# Driver.net
KiCad netlist of a schematic drawn in EasyEDA Pro
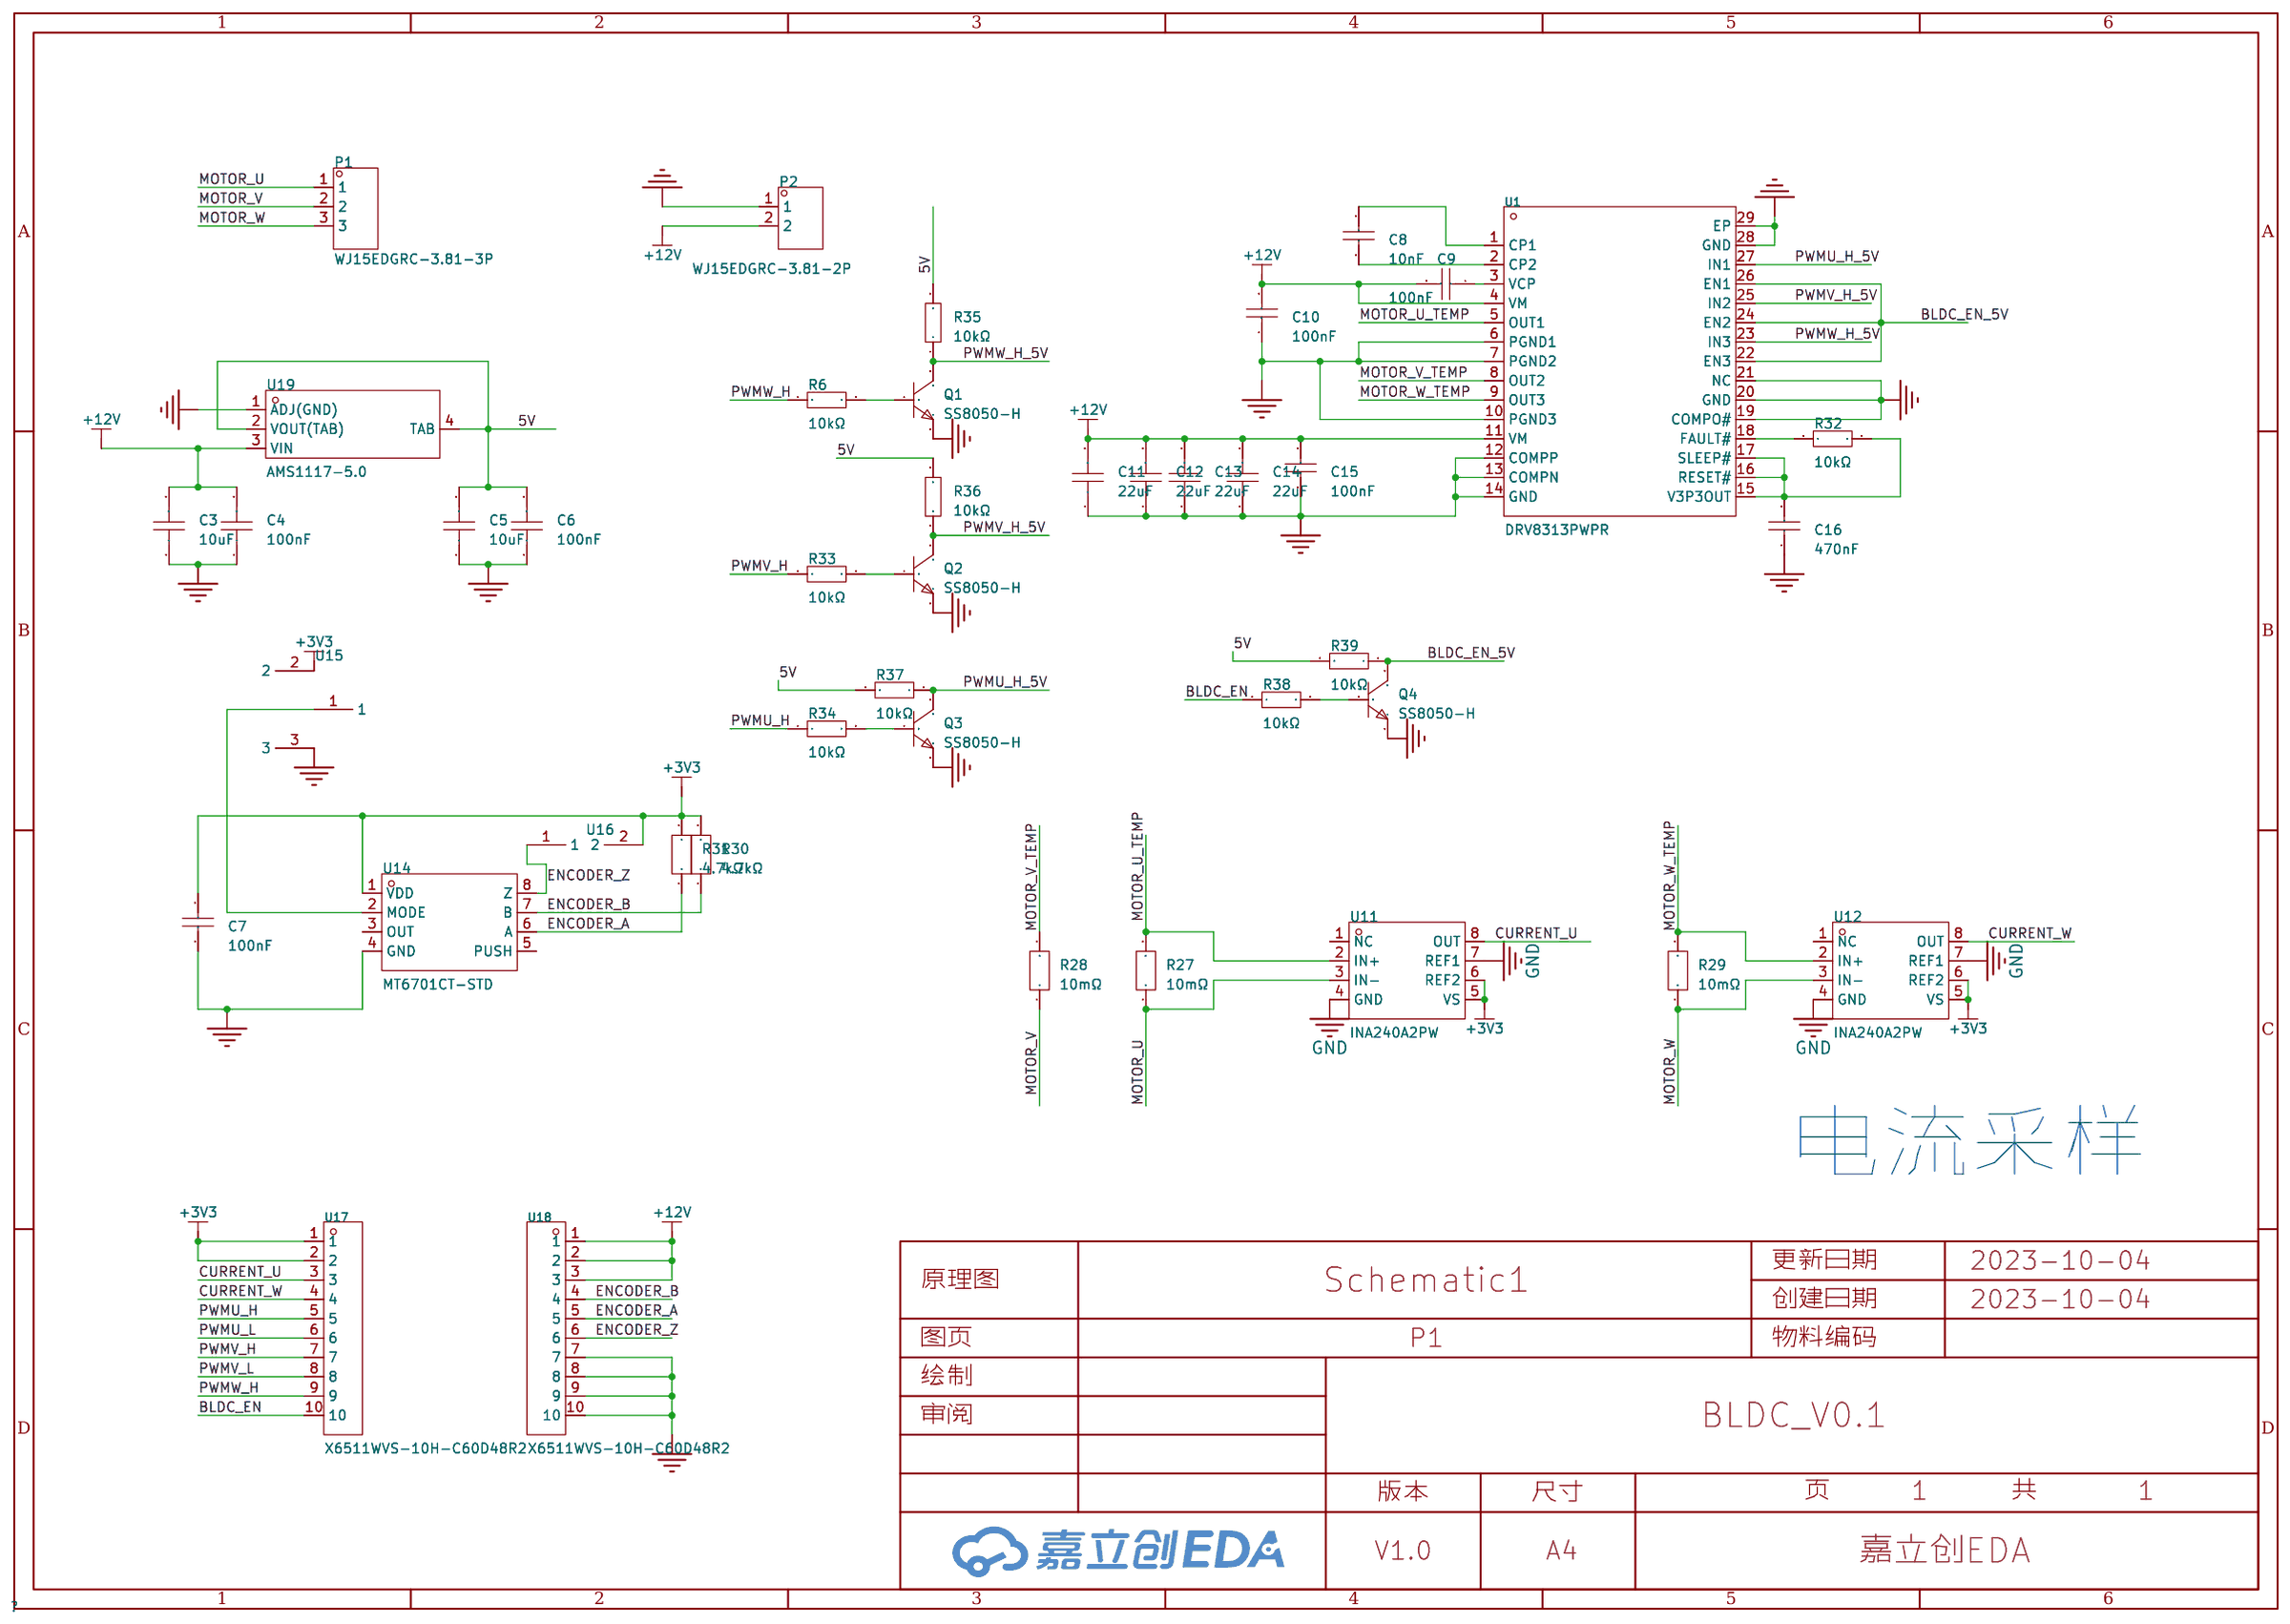
[diagram p0: schematic sheet]

(export (version "E")
  (design (tool "Eeschema 10.0.6"))
  (components
    (comp (ref "C3")
      (value "10uF")
      (footprint "easyedapro:C0603")
      (description "容值:10uF;精度:±20%;额定电压:25V;材质(温度系数):X5R;")
      (fields
        (field (name "Manufacturer Part") "CL10A106MA8NRNC")
        (field (name "Manufacturer") "SAMSUNG(三星)")
      )
      (libsource (lib "easyedapro") (part "CL10A106MA8NRNC"))
    )
    (comp (ref "C4")
      (value "100nF")
      (footprint "easyedapro:C0603")
      (description "容值:100nF;精度:±10%;额定电压:50V;材质(温度系数):X7R;")
      (fields
        (field (name "Manufacturer Part") "CC0603KRX7R9BB104")
        (field (name "Manufacturer") "YAGEO(国巨)")
      )
      (libsource (lib "easyedapro") (part "CC0603KRX7R9BB104"))
    )
    (comp (ref "C5")
      (value "10uF")
      (footprint "easyedapro:C0603")
      (description "容值:10uF;精度:±20%;额定电压:25V;材质(温度系数):X5R;")
      (fields
        (field (name "Manufacturer Part") "CL10A106MA8NRNC")
        (field (name "Manufacturer") "SAMSUNG(三星)")
      )
      (libsource (lib "easyedapro") (part "CL10A106MA8NRNC"))
    )
    (comp (ref "C6")
      (value "100nF")
      (footprint "easyedapro:C0603")
      (description "容值:100nF;精度:±10%;额定电压:50V;材质(温度系数):X7R;")
      (fields
        (field (name "Manufacturer Part") "CC0603KRX7R9BB104")
        (field (name "Manufacturer") "YAGEO(国巨)")
      )
      (libsource (lib "easyedapro") (part "CC0603KRX7R9BB104"))
    )
    (comp (ref "C7")
      (value "100nF")
      (footprint "easyedapro:C0603")
      (description "容值:100nF;精度:±10%;额定电压:50V;材质(温度系数):X7R;")
      (fields (field (name "Manufacturer Part") "0603B104K500NT") (field (name "Manufacturer") "FH(风华)"))
      (libsource (lib "easyedapro") (part "0603B104K500NT"))
    )
    (comp (ref "C8")
      (value "10nF")
      (footprint "easyedapro:C0603")
      (description "容值:10nF;精度:±10%;额定电压:50V;材质(温度系数):X7R;")
      (fields
        (field (name "Manufacturer Part") "CC0603KRX7R9BB103")
        (field (name "Manufacturer") "YAGEO(国巨)")
      )
      (libsource (lib "easyedapro") (part "CC0603KRX7R9BB103"))
    )
    (comp (ref "C9")
      (value "100nF")
      (footprint "easyedapro:C0603")
      (description "容值:100nF;精度:±10%;额定电压:50V;材质(温度系数):X7R;")
      (fields (field (name "Manufacturer Part") "0603B104K500NT") (field (name "Manufacturer") "FH(风华)"))
      (libsource (lib "easyedapro") (part "0603B104K500NT"))
    )
    (comp (ref "C10")
      (value "100nF")
      (footprint "easyedapro:C0603")
      (description "容值:100nF;精度:±10%;额定电压:50V;材质(温度系数):X7R;")
      (fields (field (name "Manufacturer Part") "0603B104K500NT") (field (name "Manufacturer") "FH(风华)"))
      (libsource (lib "easyedapro") (part "0603B104K500NT"))
    )
    (comp (ref "C11")
      (value "22uF")
      (footprint "easyedapro:C0805")
      (description "容值:22uF;精度:±20%;额定电压:25V;材质(温度系数):X5R;")
      (fields
        (field (name "Manufacturer Part") "CL21A226MAQNNNE")
        (field (name "Manufacturer") "SAMSUNG(三星)")
      )
      (libsource (lib "easyedapro") (part "CL21A226MAQNNNE"))
    )
    (comp (ref "C12")
      (value "22uF")
      (footprint "easyedapro:C0805")
      (description "容值:22uF;精度:±20%;额定电压:25V;材质(温度系数):X5R;")
      (fields
        (field (name "Manufacturer Part") "CL21A226MAQNNNE")
        (field (name "Manufacturer") "SAMSUNG(三星)")
      )
      (libsource (lib "easyedapro") (part "CL21A226MAQNNNE"))
    )
    (comp (ref "C13")
      (value "22uF")
      (footprint "easyedapro:C0805")
      (description "容值:22uF;精度:±20%;额定电压:25V;材质(温度系数):X5R;")
      (fields
        (field (name "Manufacturer Part") "CL21A226MAQNNNE")
        (field (name "Manufacturer") "SAMSUNG(三星)")
      )
      (libsource (lib "easyedapro") (part "CL21A226MAQNNNE"))
    )
    (comp (ref "C14")
      (value "22uF")
      (footprint "easyedapro:C0805")
      (description "容值:22uF;精度:±20%;额定电压:25V;材质(温度系数):X5R;")
      (fields
        (field (name "Manufacturer Part") "CL21A226MAQNNNE")
        (field (name "Manufacturer") "SAMSUNG(三星)")
      )
      (libsource (lib "easyedapro") (part "CL21A226MAQNNNE"))
    )
    (comp (ref "C15")
      (value "100nF")
      (footprint "easyedapro:C0603")
      (description "容值:100nF;精度:±10%;额定电压:50V;材质(温度系数):X7R;")
      (fields (field (name "Manufacturer Part") "0603B104K500NT") (field (name "Manufacturer") "FH(风华)"))
      (libsource (lib "easyedapro") (part "0603B104K500NT"))
    )
    (comp (ref "C16")
      (value "470nF")
      (footprint "easyedapro:C0603")
      (description "容值:470nF;精度:±10%;额定电压:25V;材质(温度系数):X7R;")
      (fields
        (field (name "Manufacturer Part") "CL10B474KA8NNNC")
        (field (name "Manufacturer") "SAMSUNG(三星)")
      )
      (libsource (lib "easyedapro") (part "CL10B474KA8NNNC"))
    )
    (comp (ref "P1")
      (value "WJ15EDGRC-3.81-3P")
      (footprint "easyedapro:CONN-TH_3P-P3.81_WJ15EDGRC-3.81-3P")
      (description "连接器类型:板端/插座-闭口;结构:1x3P;间距:3.81mm;排数:1;每排PIN数:3;安装方式:弯针;颜色:绿色;")
      (fields (field (name "Manufacturer") "KANGNEX(康奈克斯电气)"))
      (libsource (lib "easyedapro") (part "WJ15EDGRC-3.81-3P"))
    )
    (comp (ref "P2")
      (value "WJ15EDGRC-3.81-2P")
      (footprint "easyedapro:CONN-TH_2P-P3.81_WJ15EDGRC-3.81-2P")
      (description "连接器类型:板端/插座-闭口;间距:3.81mm;排数:1;每排PIN数:2;安装方式:弯针;颜色:绿色;")
      (fields (field (name "Manufacturer") "KANGNEX(康奈克斯电气)"))
      (libsource (lib "easyedapro") (part "WJ15EDGRC-3.81-2P"))
    )
    (comp (ref "Q1")
      (value "SS8050-H")
      (footprint "easyedapro:SOT-23-3_L2.9-W1.3-P1.90-LS2.4-BR")
      (description "晶体管类型:NPN;集射极击穿电压(Vceo):25V;集电极电流(Ic):1.5A;功率(Pd):300mW;直流电流增益(hFE@Ic,Vce):200@100mA,1V;")
      (fields (field (name "Manufacturer") "YANGJIE(扬杰)"))
      (libsource (lib "easyedapro") (part "SS8050-H"))
    )
    (comp (ref "Q2")
      (value "SS8050-H")
      (footprint "easyedapro:SOT-23-3_L2.9-W1.3-P1.90-LS2.4-BR")
      (description "晶体管类型:NPN;集射极击穿电压(Vceo):25V;集电极电流(Ic):1.5A;功率(Pd):300mW;直流电流增益(hFE@Ic,Vce):200@100mA,1V;")
      (fields (field (name "Manufacturer") "YANGJIE(扬杰)"))
      (libsource (lib "easyedapro") (part "SS8050-H"))
    )
    (comp (ref "Q3")
      (value "SS8050-H")
      (footprint "easyedapro:SOT-23-3_L2.9-W1.3-P1.90-LS2.4-BR")
      (description "晶体管类型:NPN;集射极击穿电压(Vceo):25V;集电极电流(Ic):1.5A;功率(Pd):300mW;直流电流增益(hFE@Ic,Vce):200@100mA,1V;")
      (fields (field (name "Manufacturer") "YANGJIE(扬杰)"))
      (libsource (lib "easyedapro") (part "SS8050-H"))
    )
    (comp (ref "Q4")
      (value "SS8050-H")
      (footprint "easyedapro:SOT-23-3_L2.9-W1.3-P1.90-LS2.4-BR")
      (description "晶体管类型:NPN;集射极击穿电压(Vceo):25V;集电极电流(Ic):1.5A;功率(Pd):300mW;直流电流增益(hFE@Ic,Vce):200@100mA,1V;")
      (fields (field (name "Manufacturer") "YANGJIE(扬杰)"))
      (libsource (lib "easyedapro") (part "SS8050-H"))
    )
    (comp (ref "R6")
      (value "10kΩ")
      (footprint "easyedapro:R0603")
      (description "电阻类型:厚膜电阻;阻值:10kΩ;精度:±1%;功率:100mW;")
      (fields (field (name "Manufacturer Part") "ERJ3EKF1002V") (field (name "Manufacturer") "PANASONIC(松下)"))
      (libsource (lib "easyedapro") (part "ERJ-3EKF1002V"))
    )
    (comp (ref "R27")
      (value "10mΩ")
      (footprint "easyedapro:RES-SMD_L6.4-W3.2-R2512")
      (description "阻值:10mΩ;功率:3W;")
      (fields
        (field (name "Manufacturer Part") "HoJLR2512-3W-10mR-1%")
        (field (name "Manufacturer") "Milliohm(毫欧)")
      )
      (libsource (lib "easyedapro") (part "HOJLR2512-3W-10MR-1%"))
    )
    (comp (ref "R28")
      (value "10mΩ")
      (footprint "easyedapro:RES-SMD_L6.4-W3.2-R2512")
      (description "阻值:10mΩ;功率:3W;")
      (fields
        (field (name "Manufacturer Part") "HoJLR2512-3W-10mR-1%")
        (field (name "Manufacturer") "Milliohm(毫欧)")
      )
      (libsource (lib "easyedapro") (part "HOJLR2512-3W-10MR-1%"))
    )
    (comp (ref "R29")
      (value "10mΩ")
      (footprint "easyedapro:RES-SMD_L6.4-W3.2-R2512")
      (description "阻值:10mΩ;功率:3W;")
      (fields
        (field (name "Manufacturer Part") "HoJLR2512-3W-10mR-1%")
        (field (name "Manufacturer") "Milliohm(毫欧)")
      )
      (libsource (lib "easyedapro") (part "HOJLR2512-3W-10MR-1%"))
    )
    (comp (ref "R30")
      (value "4.7kΩ")
      (footprint "easyedapro:R0603")
      (description "阻值:4.7kΩ;功率:100mW;")
      (fields
        (field (name "Manufacturer Part") "HoLTT0603-1/10W-4.7K-1%")
        (field (name "Manufacturer") "Milliohm(毫欧)")
      )
      (libsource (lib "easyedapro") (part "HOLTT0603-1/10W-4.7K-1%"))
    )
    (comp (ref "R31")
      (value "4.7kΩ")
      (footprint "easyedapro:R0603")
      (description "阻值:4.7kΩ;功率:100mW;")
      (fields
        (field (name "Manufacturer Part") "HoLTT0603-1/10W-4.7K-1%")
        (field (name "Manufacturer") "Milliohm(毫欧)")
      )
      (libsource (lib "easyedapro") (part "HOLTT0603-1/10W-4.7K-1%"))
    )
    (comp (ref "R32")
      (value "10kΩ")
      (footprint "easyedapro:R0603")
      (description "电阻类型:厚膜电阻;阻值:10kΩ;精度:±1%;功率:100mW;")
      (fields
        (field (name "Manufacturer Part") "0603WAF1002T5E")
        (field (name "Manufacturer") "UNI-ROYAL(厚声)")
      )
      (libsource (lib "easyedapro") (part "0603WAF1002T5E"))
    )
    (comp (ref "R33")
      (value "10kΩ")
      (footprint "easyedapro:R0603")
      (description "电阻类型:厚膜电阻;阻值:10kΩ;精度:±1%;功率:100mW;")
      (fields (field (name "Manufacturer Part") "ERJ3EKF1002V") (field (name "Manufacturer") "PANASONIC(松下)"))
      (libsource (lib "easyedapro") (part "ERJ-3EKF1002V"))
    )
    (comp (ref "R34")
      (value "10kΩ")
      (footprint "easyedapro:R0603")
      (description "电阻类型:厚膜电阻;阻值:10kΩ;精度:±1%;功率:100mW;")
      (fields (field (name "Manufacturer Part") "ERJ3EKF1002V") (field (name "Manufacturer") "PANASONIC(松下)"))
      (libsource (lib "easyedapro") (part "ERJ-3EKF1002V"))
    )
    (comp (ref "R35")
      (value "10kΩ")
      (footprint "easyedapro:R0603")
      (description "电阻类型:厚膜电阻;阻值:10kΩ;精度:±1%;功率:100mW;")
      (fields (field (name "Manufacturer Part") "ERJ3EKF1002V") (field (name "Manufacturer") "PANASONIC(松下)"))
      (libsource (lib "easyedapro") (part "ERJ-3EKF1002V"))
    )
    (comp (ref "R36")
      (value "10kΩ")
      (footprint "easyedapro:R0603")
      (description "电阻类型:厚膜电阻;阻值:10kΩ;精度:±1%;功率:100mW;")
      (fields (field (name "Manufacturer Part") "ERJ3EKF1002V") (field (name "Manufacturer") "PANASONIC(松下)"))
      (libsource (lib "easyedapro") (part "ERJ-3EKF1002V"))
    )
    (comp (ref "R37")
      (value "10kΩ")
      (footprint "easyedapro:R0603")
      (description "电阻类型:厚膜电阻;阻值:10kΩ;精度:±1%;功率:100mW;")
      (fields (field (name "Manufacturer Part") "ERJ3EKF1002V") (field (name "Manufacturer") "PANASONIC(松下)"))
      (libsource (lib "easyedapro") (part "ERJ-3EKF1002V"))
    )
    (comp (ref "R38")
      (value "10kΩ")
      (footprint "easyedapro:R0603")
      (description "电阻类型:厚膜电阻;阻值:10kΩ;精度:±1%;功率:100mW;")
      (fields (field (name "Manufacturer Part") "ERJ3EKF1002V") (field (name "Manufacturer") "PANASONIC(松下)"))
      (libsource (lib "easyedapro") (part "ERJ-3EKF1002V"))
    )
    (comp (ref "R39")
      (value "10kΩ")
      (footprint "easyedapro:R0603")
      (description "电阻类型:厚膜电阻;阻值:10kΩ;精度:±1%;功率:100mW;")
      (fields (field (name "Manufacturer Part") "ERJ3EKF1002V") (field (name "Manufacturer") "PANASONIC(松下)"))
      (libsource (lib "easyedapro") (part "ERJ-3EKF1002V"))
    )
    (comp (ref "U1")
      (value "DRV8313PWPR")
      (footprint "easyedapro:HTSSOP-28_L9.8-W4.5-P0.65-LS6.6-BL-EP")
      (description "类型:无刷直流BLDC;电源电压:8V~60V;输出电流:-;接口:并行;")
      (fields (field (name "Manufacturer") "TI(德州仪器)"))
      (libsource (lib "easyedapro") (part "DRV8313PWPR"))
    )
    (comp (ref "U11")
      (value "INA240A2PW")
      (footprint "easyedapro:TSSOP-8_L4.4-W3.0-P0.65-LS6.4-BR")
      (description "具有增强的 PWM 抑制能力的 -4V 至 80V、双向、超精密电流感应放大器 8-TSSOP -40 to 125")
      (fields (field (name "Manufacturer") "TI(德州仪器)"))
      (libsource (lib "easyedapro") (part "INA240A2PW"))
    )
    (comp (ref "U12")
      (value "INA240A2PW")
      (footprint "easyedapro:TSSOP-8_L4.4-W3.0-P0.65-LS6.4-BR")
      (description "具有增强的 PWM 抑制能力的 -4V 至 80V、双向、超精密电流感应放大器 8-TSSOP -40 to 125")
      (fields (field (name "Manufacturer") "TI(德州仪器)"))
      (libsource (lib "easyedapro") (part "INA240A2PW"))
    )
    (comp (ref "U14")
      (value "MT6701CT-STD")
      (footprint "easyedapro:SOP-8_L4.9-W3.9-P1.27-LS6.0-BL")
      (description "磁性编码器 磁性编码开关 磁性角度检测IC 可编程磁性角度位置芯片")
      (fields (field (name "Manufacturer") "MagnTek(麦歌恩)"))
      (libsource (lib "easyedapro") (part "MT6701CT-STD"))
    )
    (comp (ref "U15")
      (value "~")
      (footprint "easyedapro:三端短接调试")
      (libsource (lib "easyedapro") (part "三段短接调试"))
    )
    (comp (ref "U16")
      (value "~")
      (footprint "easyedapro:两端短接调试位")
      (libsource (lib "easyedapro") (part "两端短接调试位"))
    )
    (comp (ref "U17")
      (value "X6511WVS-10H-C60D48R2")
      (footprint "easyedapro:HDR-SMD_10P-P2.54-V-M-LS4.8_R2")
      (fields (field (name "Manufacturer") "XKB Connectivity(中国星坤)"))
      (libsource (lib "easyedapro") (part "X6511WVS-10H-C60D48R2"))
    )
    (comp (ref "U18")
      (value "X6511WVS-10H-C60D48R2")
      (footprint "easyedapro:HDR-SMD_10P-P2.54-V-M-LS4.8_R2")
      (fields (field (name "Manufacturer") "XKB Connectivity(中国星坤)"))
      (libsource (lib "easyedapro") (part "X6511WVS-10H-C60D48R2"))
    )
    (comp (ref "U19")
      (value "AMS1117-5.0")
      (footprint "easyedapro:SOT-223_L6.7-W3.5-P2.30-BR")
      (description "输出类型:固定;输出极性:正;最大输入电压:18V;输出电压:5V;输出电流:1A;电源纹波抑制比(PSRR):60dB@(120Hz);")
      (fields (field (name "Manufacturer") "UMW(广东友台半导体)"))
      (libsource (lib "easyedapro") (part "AMS1117-5.0_C347223"))
    )
  )
  (nets
    (net (code "1") (name "+3V3") (class "Default")
      (node (ref "C7") (pin "2") (pinfunction "2_2") (pintype "input"))
      (node (ref "R30") (pin "2") (pinfunction "2_2") (pintype "input"))
      (node (ref "R31") (pin "2") (pinfunction "2_2") (pintype "input"))
      (node (ref "U11") (pin "5") (pinfunction "VS_5") (pintype "input"))
      (node (ref "U11") (pin "6") (pinfunction "REF2_6") (pintype "input"))
      (node (ref "U12") (pin "5") (pinfunction "VS_5") (pintype "input"))
      (node (ref "U12") (pin "6") (pinfunction "REF2_6") (pintype "input"))
      (node (ref "U14") (pin "1") (pinfunction "VDD_1") (pintype "input"))
      (node (ref "U15") (pin "2") (pinfunction "2_2") (pintype "input"))
      (node (ref "U16") (pin "2") (pinfunction "2_2") (pintype "input"))
      (node (ref "U17") (pin "1") (pinfunction "1_1") (pintype "input"))
      (node (ref "U17") (pin "2") (pinfunction "2_2") (pintype "input"))
    )
    (net (code "2") (name "+12V") (class "Default")
      (node (ref "C10") (pin "2") (pinfunction "2_2") (pintype "input"))
      (node (ref "C11") (pin "2") (pinfunction "2_2") (pintype "input"))
      (node (ref "C12") (pin "2") (pinfunction "2_2") (pintype "input"))
      (node (ref "C13") (pin "2") (pinfunction "2_2") (pintype "input"))
      (node (ref "C14") (pin "2") (pinfunction "2_2") (pintype "input"))
      (node (ref "C15") (pin "1") (pinfunction "1_1") (pintype "input"))
      (node (ref "C3") (pin "2") (pinfunction "2_2") (pintype "input"))
      (node (ref "C4") (pin "2") (pinfunction "2_2") (pintype "input"))
      (node (ref "C9") (pin "2") (pinfunction "2_2") (pintype "input"))
      (node (ref "P2") (pin "2") (pinfunction "2_2") (pintype "input"))
      (node (ref "U1") (pin "11") (pinfunction "VM_11") (pintype "input"))
      (node (ref "U1") (pin "4") (pinfunction "VM_4") (pintype "input"))
      (node (ref "U18") (pin "1") (pinfunction "1_1") (pintype "input"))
      (node (ref "U18") (pin "2") (pinfunction "2_2") (pintype "input"))
      (node (ref "U18") (pin "3") (pinfunction "3_3") (pintype "input"))
      (node (ref "U19") (pin "3") (pinfunction "VIN_3") (pintype "input"))
    )
    (net (code "3") (name "/5V") (class "Default")
      (node (ref "C5") (pin "2") (pinfunction "2_2") (pintype "input"))
      (node (ref "C6") (pin "2") (pinfunction "2_2") (pintype "input"))
      (node (ref "R35") (pin "2") (pinfunction "2_2") (pintype "input"))
      (node (ref "R36") (pin "2") (pinfunction "2_2") (pintype "input"))
      (node (ref "R37") (pin "2") (pinfunction "2_2") (pintype "input"))
      (node (ref "R39") (pin "2") (pinfunction "2_2") (pintype "input"))
      (node (ref "U19") (pin "2") (pinfunction "VOUT(TAB)_2") (pintype "input"))
      (node (ref "U19") (pin "4") (pinfunction "TAB_4") (pintype "input"))
    )
    (net (code "4") (name "/BLDC_EN") (class "Default")
      (node (ref "R38") (pin "1") (pinfunction "1_1") (pintype "input"))
      (node (ref "U17") (pin "10") (pinfunction "10_10") (pintype "input"))
    )
    (net (code "5") (name "/BLDC_EN_5V") (class "Default")
      (node (ref "Q4") (pin "3") (pinfunction "C_3") (pintype "input"))
      (node (ref "R39") (pin "1") (pinfunction "1_1") (pintype "input"))
      (node (ref "U1") (pin "22") (pinfunction "EN3_22") (pintype "input"))
      (node (ref "U1") (pin "24") (pinfunction "EN2_24") (pintype "input"))
      (node (ref "U1") (pin "26") (pinfunction "EN1_26") (pintype "input"))
    )
    (net (code "6") (name "/CURRENT_U") (class "Default")
      (node (ref "U11") (pin "8") (pinfunction "OUT_8") (pintype "input"))
      (node (ref "U17") (pin "3") (pinfunction "3_3") (pintype "input"))
    )
    (net (code "7") (name "/CURRENT_W") (class "Default")
      (node (ref "U12") (pin "8") (pinfunction "OUT_8") (pintype "input"))
      (node (ref "U17") (pin "4") (pinfunction "4_4") (pintype "input"))
    )
    (net (code "8") (name "/ENCODER_A") (class "Default")
      (node (ref "R31") (pin "1") (pinfunction "1_1") (pintype "input"))
      (node (ref "U14") (pin "6") (pinfunction "A_6") (pintype "input"))
      (node (ref "U18") (pin "5") (pinfunction "5_5") (pintype "input"))
    )
    (net (code "9") (name "/ENCODER_B") (class "Default")
      (node (ref "R30") (pin "1") (pinfunction "1_1") (pintype "input"))
      (node (ref "U14") (pin "7") (pinfunction "B_7") (pintype "input"))
      (node (ref "U18") (pin "4") (pinfunction "4_4") (pintype "input"))
    )
    (net (code "10") (name "/ENCODER_Z") (class "Default")
      (node (ref "U14") (pin "8") (pinfunction "Z_8") (pintype "input"))
      (node (ref "U16") (pin "1") (pinfunction "1_1") (pintype "input"))
      (node (ref "U18") (pin "6") (pinfunction "6_6") (pintype "input"))
    )
    (net (code "11") (name "/MOTOR_U") (class "Default")
      (node (ref "P1") (pin "1") (pinfunction "1_1") (pintype "input"))
      (node (ref "R27") (pin "1") (pinfunction "1_1") (pintype "input"))
      (node (ref "U11") (pin "3") (pinfunction "IN-_3") (pintype "input"))
    )
    (net (code "12") (name "/MOTOR_U_TEMP") (class "Default")
      (node (ref "R27") (pin "2") (pinfunction "2_2") (pintype "input"))
      (node (ref "U1") (pin "5") (pinfunction "OUT1_5") (pintype "input"))
      (node (ref "U11") (pin "2") (pinfunction "IN+_2") (pintype "input"))
    )
    (net (code "13") (name "/MOTOR_V") (class "Default")
      (node (ref "P1") (pin "2") (pinfunction "2_2") (pintype "input"))
      (node (ref "R28") (pin "1") (pinfunction "1_1") (pintype "input"))
    )
    (net (code "14") (name "/MOTOR_V_TEMP") (class "Default")
      (node (ref "R28") (pin "2") (pinfunction "2_2") (pintype "input"))
      (node (ref "U1") (pin "8") (pinfunction "OUT2_8") (pintype "input"))
    )
    (net (code "15") (name "/MOTOR_W") (class "Default")
      (node (ref "P1") (pin "3") (pinfunction "3_3") (pintype "input"))
      (node (ref "R29") (pin "1") (pinfunction "1_1") (pintype "input"))
      (node (ref "U12") (pin "3") (pinfunction "IN-_3") (pintype "input"))
    )
    (net (code "16") (name "/MOTOR_W_TEMP") (class "Default")
      (node (ref "R29") (pin "2") (pinfunction "2_2") (pintype "input"))
      (node (ref "U1") (pin "9") (pinfunction "OUT3_9") (pintype "input"))
      (node (ref "U12") (pin "2") (pinfunction "IN+_2") (pintype "input"))
    )
    (net (code "17") (name "/PWMU_H") (class "Default")
      (node (ref "R34") (pin "1") (pinfunction "1_1") (pintype "input"))
      (node (ref "U17") (pin "5") (pinfunction "5_5") (pintype "input"))
    )
    (net (code "18") (name "/PWMU_H_5V") (class "Default")
      (node (ref "Q3") (pin "3") (pinfunction "C_3") (pintype "input"))
      (node (ref "R37") (pin "1") (pinfunction "1_1") (pintype "input"))
      (node (ref "U1") (pin "27") (pinfunction "IN1_27") (pintype "input"))
    )
    (net (code "19") (name "/PWMU_L") (class "Default")
      (node (ref "U17") (pin "6") (pinfunction "6_6") (pintype "input"))
    )
    (net (code "20") (name "/PWMV_H") (class "Default")
      (node (ref "R33") (pin "1") (pinfunction "1_1") (pintype "input"))
      (node (ref "U17") (pin "7") (pinfunction "7_7") (pintype "input"))
    )
    (net (code "21") (name "/PWMV_H_5V") (class "Default")
      (node (ref "Q2") (pin "3") (pinfunction "C_3") (pintype "input"))
      (node (ref "R36") (pin "1") (pinfunction "1_1") (pintype "input"))
      (node (ref "U1") (pin "25") (pinfunction "IN2_25") (pintype "input"))
    )
    (net (code "22") (name "/PWMV_L") (class "Default")
      (node (ref "U17") (pin "8") (pinfunction "8_8") (pintype "input"))
    )
    (net (code "23") (name "/PWMW_H") (class "Default")
      (node (ref "R6") (pin "1") (pinfunction "1_1") (pintype "input"))
      (node (ref "U17") (pin "9") (pinfunction "9_9") (pintype "input"))
    )
    (net (code "24") (name "/PWMW_H_5V") (class "Default")
      (node (ref "Q1") (pin "3") (pinfunction "C_3") (pintype "input"))
      (node (ref "R35") (pin "1") (pinfunction "1_1") (pintype "input"))
      (node (ref "U1") (pin "23") (pinfunction "IN3_23") (pintype "input"))
    )
    (net (code "25") (name "GND") (class "Default")
      (node (ref "C10") (pin "1") (pinfunction "1_1") (pintype "input"))
      (node (ref "C11") (pin "1") (pinfunction "1_1") (pintype "input"))
      (node (ref "C12") (pin "1") (pinfunction "1_1") (pintype "input"))
      (node (ref "C13") (pin "1") (pinfunction "1_1") (pintype "input"))
      (node (ref "C14") (pin "1") (pinfunction "1_1") (pintype "input"))
      (node (ref "C15") (pin "2") (pinfunction "2_2") (pintype "input"))
      (node (ref "C16") (pin "1") (pinfunction "1_1") (pintype "input"))
      (node (ref "C3") (pin "1") (pinfunction "1_1") (pintype "input"))
      (node (ref "C4") (pin "1") (pinfunction "1_1") (pintype "input"))
      (node (ref "C5") (pin "1") (pinfunction "1_1") (pintype "input"))
      (node (ref "C6") (pin "1") (pinfunction "1_1") (pintype "input"))
      (node (ref "C7") (pin "1") (pinfunction "1_1") (pintype "input"))
      (node (ref "P2") (pin "1") (pinfunction "1_1") (pintype "input"))
      (node (ref "Q1") (pin "2") (pinfunction "E_2") (pintype "input"))
      (node (ref "Q2") (pin "2") (pinfunction "E_2") (pintype "input"))
      (node (ref "Q3") (pin "2") (pinfunction "E_2") (pintype "input"))
      (node (ref "Q4") (pin "2") (pinfunction "E_2") (pintype "input"))
      (node (ref "U1") (pin "10") (pinfunction "PGND3_10") (pintype "input"))
      (node (ref "U1") (pin "12") (pinfunction "COMPP_12") (pintype "input"))
      (node (ref "U1") (pin "13") (pinfunction "COMPN_13") (pintype "input"))
      (node (ref "U1") (pin "14") (pinfunction "GND_14") (pintype "input"))
      (node (ref "U1") (pin "19") (pinfunction "COMPO#_19") (pintype "input"))
      (node (ref "U1") (pin "20") (pinfunction "GND_20") (pintype "input"))
      (node (ref "U1") (pin "21") (pinfunction "NC_21") (pintype "input"))
      (node (ref "U1") (pin "28") (pinfunction "GND_28") (pintype "input"))
      (node (ref "U1") (pin "29") (pinfunction "EP_29") (pintype "input"))
      (node (ref "U1") (pin "6") (pinfunction "PGND1_6") (pintype "input"))
      (node (ref "U1") (pin "7") (pinfunction "PGND2_7") (pintype "input"))
      (node (ref "U11") (pin "4") (pinfunction "GND_4") (pintype "input"))
      (node (ref "U11") (pin "7") (pinfunction "REF1_7") (pintype "input"))
      (node (ref "U12") (pin "4") (pinfunction "GND_4") (pintype "input"))
      (node (ref "U12") (pin "7") (pinfunction "REF1_7") (pintype "input"))
      (node (ref "U14") (pin "4") (pinfunction "GND_4") (pintype "input"))
      (node (ref "U15") (pin "3") (pinfunction "3_3") (pintype "input"))
      (node (ref "U18") (pin "10") (pinfunction "10_10") (pintype "input"))
      (node (ref "U18") (pin "7") (pinfunction "7_7") (pintype "input"))
      (node (ref "U18") (pin "8") (pinfunction "8_8") (pintype "input"))
      (node (ref "U18") (pin "9") (pinfunction "9_9") (pintype "input"))
      (node (ref "U19") (pin "1") (pinfunction "ADJ(GND)_1") (pintype "input"))
    )
    (net (code "26") (name "Net-(Q1-B)") (class "Default")
      (node (ref "Q1") (pin "1") (pinfunction "B_1") (pintype "input"))
      (node (ref "R6") (pin "2") (pinfunction "2_2") (pintype "input"))
    )
    (net (code "27") (name "Net-(Q2-B)") (class "Default")
      (node (ref "Q2") (pin "1") (pinfunction "B_1") (pintype "input"))
      (node (ref "R33") (pin "2") (pinfunction "2_2") (pintype "input"))
    )
    (net (code "28") (name "Net-(Q3-B)") (class "Default")
      (node (ref "Q3") (pin "1") (pinfunction "B_1") (pintype "input"))
      (node (ref "R34") (pin "2") (pinfunction "2_2") (pintype "input"))
    )
    (net (code "29") (name "Net-(Q4-B)") (class "Default")
      (node (ref "Q4") (pin "1") (pinfunction "B_1") (pintype "input"))
      (node (ref "R38") (pin "2") (pinfunction "2_2") (pintype "input"))
    )
    (net (code "30") (name "Net-(U1-CP1)") (class "Default")
      (node (ref "C8") (pin "2") (pinfunction "2_2") (pintype "input"))
      (node (ref "U1") (pin "1") (pinfunction "CP1_1") (pintype "input"))
    )
    (net (code "31") (name "Net-(U1-CP2)") (class "Default")
      (node (ref "C8") (pin "1") (pinfunction "1_1") (pintype "input"))
      (node (ref "U1") (pin "2") (pinfunction "CP2_2") (pintype "input"))
    )
    (net (code "32") (name "Net-(U1-FAULT#)") (class "Default")
      (node (ref "R32") (pin "2") (pinfunction "2_2") (pintype "input"))
      (node (ref "U1") (pin "18") (pinfunction "FAULT#_18") (pintype "input"))
    )
    (net (code "33") (name "Net-(U1-RESET#)") (class "Default")
      (node (ref "C16") (pin "2") (pinfunction "2_2") (pintype "input"))
      (node (ref "R32") (pin "1") (pinfunction "1_1") (pintype "input"))
      (node (ref "U1") (pin "15") (pinfunction "V3P3OUT_15") (pintype "input"))
      (node (ref "U1") (pin "16") (pinfunction "RESET#_16") (pintype "input"))
      (node (ref "U1") (pin "17") (pinfunction "SLEEP#_17") (pintype "input"))
    )
    (net (code "34") (name "Net-(U1-VCP)") (class "Default")
      (node (ref "C9") (pin "1") (pinfunction "1_1") (pintype "input"))
      (node (ref "U1") (pin "3") (pinfunction "VCP_3") (pintype "input"))
    )
    (net (code "35") (name "Net-(U14-MODE)") (class "Default")
      (node (ref "U14") (pin "2") (pinfunction "MODE_2") (pintype "input"))
      (node (ref "U15") (pin "1") (pinfunction "1_1") (pintype "input"))
    )
    (net (code "36") (name "unconnected-(U11-NC-Pad1)") (class "Default")
      (node (ref "U11") (pin "1") (pinfunction "NC_1") (pintype "input"))
    )
    (net (code "37") (name "unconnected-(U12-NC-Pad1)") (class "Default")
      (node (ref "U12") (pin "1") (pinfunction "NC_1") (pintype "input"))
    )
    (net (code "38") (name "unconnected-(U14-OUT-Pad3)") (class "Default")
      (node (ref "U14") (pin "3") (pinfunction "OUT_3") (pintype "input"))
    )
    (net (code "39") (name "unconnected-(U14-PUSH-Pad5)") (class "Default")
      (node (ref "U14") (pin "5") (pinfunction "PUSH_5") (pintype "input"))
    )
  )
)
